# STM32_Smart.net
KiCad netlist of a schematic drawn in Altium Designer
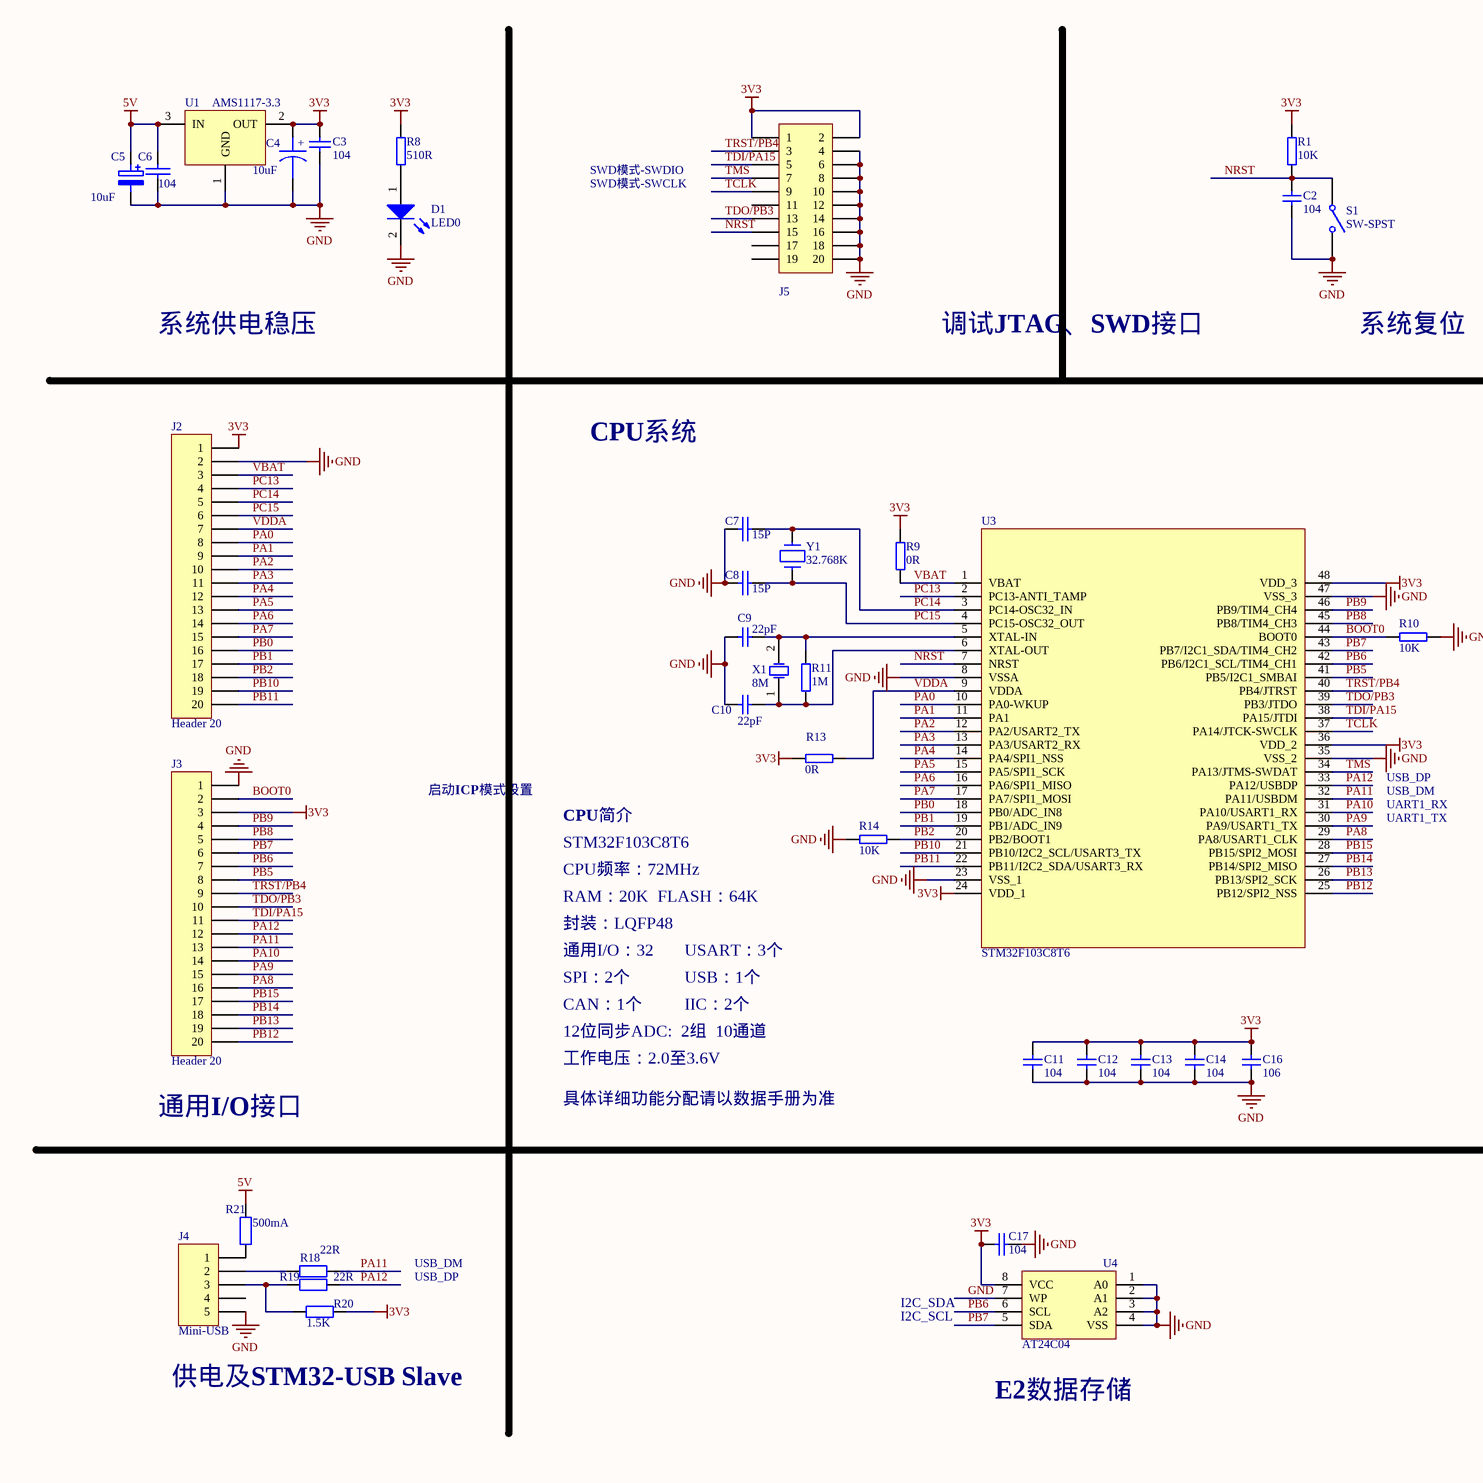
[diagram p0: STM32_Smart.SchDoc, left]
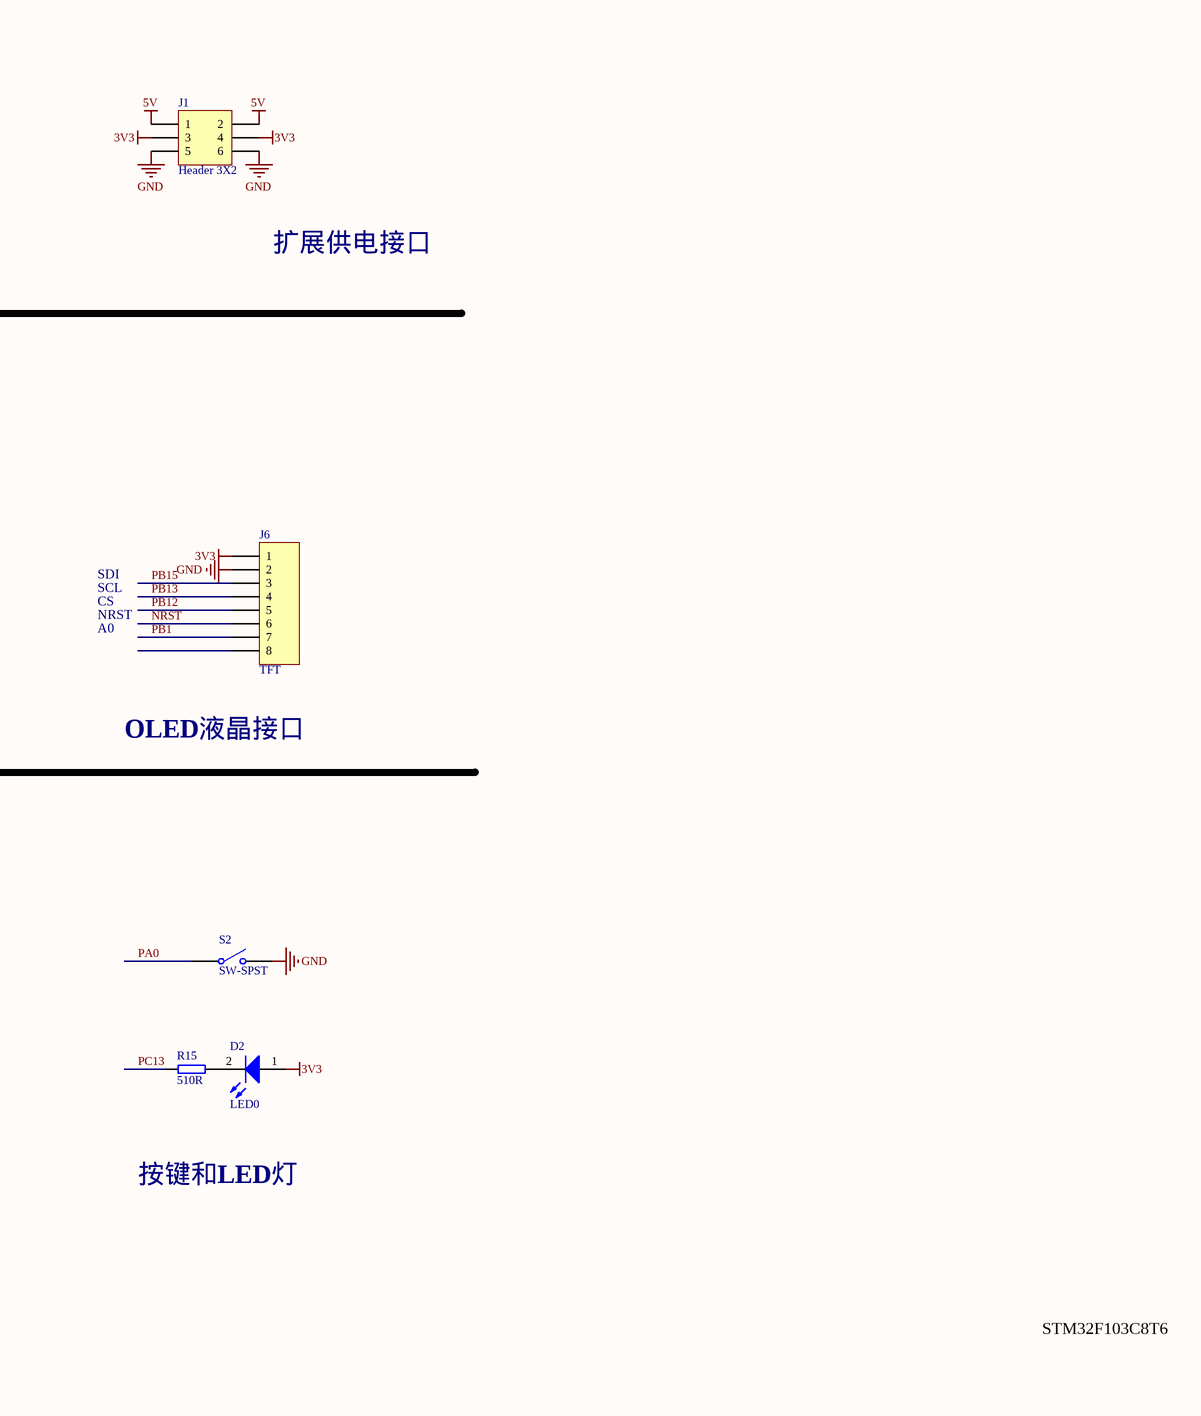
[diagram p1: STM32_Smart.SchDoc, right]

(export (version "E")
  (design (tool "Eeschema 10.0.6"))
  (components
    (comp (ref "C2")
      (value "104")
      (footprint "RC0603")
      (description "Capacitor")
      (fields (field (name "PUBLISHER") "ZL_A0OFFICE"))
      (libsource (lib "CommomDevices") (part "CAP1"))
    )
    (comp (ref "C3")
      (value "104")
      (footprint "RC0603")
      (description "Capacitor")
      (fields (field (name "PUBLISHER") "Altium Limited"))
      (libsource (lib "*") (part "Cap"))
    )
    (comp (ref "C4")
      (value "10uF")
      (footprint "RC0805")
      (description "Capacitor")
      (libsource (lib "*") (part "CAPACITOR POL"))
    )
    (comp (ref "C5") (value "10uF") (footprint "RC0805") (libsource (lib "*") (part "ELECTRO2")))
    (comp (ref "C6")
      (value "104")
      (footprint "RC0603")
      (description "Capacitor")
      (libsource (lib "") (part "CAP_1"))
    )
    (comp (ref "C7") (value "15P") (footprint "RC0603") (libsource (lib "*") (part "CAP")))
    (comp (ref "C8") (value "15P") (footprint "RC0603") (libsource (lib "*") (part "CAP")))
    (comp (ref "C9")
      (value "22pF")
      (footprint "RC0603")
      (description "Capacitor")
      (fields (field (name "PUBLISHER") "ZL_A0OFFICE"))
      (libsource (lib "CommomDevices") (part "CAP1"))
    )
    (comp (ref "C10")
      (value "22pF")
      (footprint "RC0603")
      (description "Capacitor")
      (fields (field (name "PUBLISHER") "ZL_A0OFFICE"))
      (libsource (lib "CommomDevices") (part "CAP1"))
    )
    (comp (ref "C11")
      (value "104")
      (footprint "RC0603")
      (description "Capacitor")
      (fields (field (name "PUBLISHER") "ZL_A0OFFICE"))
      (libsource (lib "CommomDevices") (part "CAP1"))
    )
    (comp (ref "C12")
      (value "104")
      (footprint "RC0603")
      (description "Capacitor")
      (fields (field (name "PUBLISHER") "ZL_A0OFFICE"))
      (libsource (lib "CommomDevices") (part "CAP1"))
    )
    (comp (ref "C13")
      (value "104")
      (footprint "RC0603")
      (description "Capacitor")
      (fields (field (name "PUBLISHER") "ZL_A0OFFICE"))
      (libsource (lib "CommomDevices") (part "CAP1"))
    )
    (comp (ref "C14")
      (value "104")
      (footprint "RC0603")
      (description "Capacitor")
      (fields (field (name "PUBLISHER") "ZL_A0OFFICE"))
      (libsource (lib "CommomDevices") (part "CAP1"))
    )
    (comp (ref "C16")
      (value "106")
      (footprint "RC0805")
      (description "Capacitor")
      (fields (field (name "PUBLISHER") "ZL_A0OFFICE"))
      (libsource (lib "CommomDevices") (part "CAP1"))
    )
    (comp (ref "C17")
      (value "104")
      (footprint "RC0603")
      (description "Capacitor")
      (libsource (lib "Miscellaneous Devices") (part "Cap"))
    )
    (comp (ref "D1")
      (value "LED0")
      (footprint "LED0805")
      (description "Typical INFRARED GaAs LED")
      (libsource (lib "Miscellaneous Devices") (part "LED0"))
    )
    (comp (ref "D2")
      (value "LED0")
      (footprint "LED0805")
      (description "Typical INFRARED GaAs LED")
      (libsource (lib "Miscellaneous Devices") (part "LED0"))
    )
    (comp (ref "J1")
      (value "Header 3X2")
      (footprint "IDE3X2-2.54")
      (description "Header, 3-Pin, Dual row")
      (fields (field (name "PUBLISHER") "Altium Limited"))
      (libsource (lib "Miscellaneous Connectors") (part "Header 3X2"))
    )
    (comp (ref "J2")
      (value "Header 20")
      (footprint "HDR1X20")
      (description "Header, 20-Pin")
      (fields (field (name "PUBLISHER") "Altium Limited"))
      (libsource (lib "Miscellaneous Connectors") (part "Header 20"))
    )
    (comp (ref "J3")
      (value "Header 20")
      (footprint "HDR1X20")
      (description "Header, 20-Pin")
      (fields (field (name "PUBLISHER") "Altium Limited"))
      (libsource (lib "Miscellaneous Connectors") (part "Header 20"))
    )
    (comp (ref "J4")
      (value "Mini-USB")
      (footprint "mini_USB")
      (description "Header, 5-Pin")
      (libsource (lib "Miscellaneous Connectors") (part "Header 5"))
    )
    (comp (ref "J5")
      (value "~")
      (footprint "JTAG20P")
      (description "Header, 10-Pin, Dual row, Right Angle")
      (fields (field (name "PUBLISHER") "Altium Limited"))
      (libsource (lib "Miscellaneous Connectors") (part "Header 10X2H"))
    )
    (comp (ref "J6")
      (value "TFT")
      (footprint "HDR1X8")
      (description "Header, 8-Pin")
      (libsource (lib "Miscellaneous Connectors") (part "Header 8"))
    )
    (comp (ref "R1") (value "10K") (footprint "RC0603") (libsource (lib "ZIBO V2.0_Main") (part "R")))
    (comp (ref "R8") (value "510R") (footprint "RC0603") (libsource (lib "ZIBO V2.0_Main") (part "R")))
    (comp (ref "R9") (value "0R") (footprint "RC0603") (libsource (lib "ZIBO V2.0_Main") (part "R")))
    (comp (ref "R10") (value "10K") (footprint "RC0603") (libsource (lib "ZIBO V2.0_Main") (part "R")))
    (comp (ref "R11") (value "1M") (footprint "RC0603") (libsource (lib "ZIBO V2.0_Main") (part "R")))
    (comp (ref "R13") (value "0R") (footprint "RC0603") (libsource (lib "ZIBO V2.0_Main") (part "R")))
    (comp (ref "R14") (value "10K") (footprint "RC0603") (libsource (lib "ZIBO V2.0_Main") (part "R")))
    (comp (ref "R15") (value "510R") (footprint "RC0603") (libsource (lib "ZIBO V2.0_Main") (part "R")))
    (comp (ref "R18")
      (value "22R")
      (footprint "RC0603")
      (description "Resistor")
      (libsource (lib "Miscellaneous Devices") (part "Res2"))
    )
    (comp (ref "R19")
      (value "22R")
      (footprint "RC0603")
      (description "Resistor")
      (libsource (lib "Miscellaneous Devices") (part "Res2"))
    )
    (comp (ref "R20")
      (value "1.5K")
      (footprint "RC0603")
      (description "Resistor")
      (libsource (lib "Miscellaneous Devices") (part "Res2"))
    )
    (comp (ref "R21")
      (value "500mA")
      (footprint "RC0805")
      (description "Resistor")
      (libsource (lib "") (part "Res2_1"))
    )
    (comp (ref "S1")
      (value "SW-SPST")
      (footprint "SMT-KEY")
      (description "Single-Pole, Single-Throw Switch")
      (libsource (lib "Miscellaneous Devices") (part "SW-SPST"))
    )
    (comp (ref "S2")
      (value "SW-SPST")
      (footprint "SMT-KEY")
      (description "Single-Pole, Single-Throw Switch")
      (libsource (lib "Miscellaneous Devices") (part "SW-SPST"))
    )
    (comp (ref "U1")
      (value "AMS1117-3.3")
      (footprint "SOT223")
      (libsource (lib "Newcapec9263_Board_NEW") (part "LT1085CM-3.3"))
    )
    (comp (ref "U3")
      (value "STM32F103C8T6")
      (footprint "LQFP48")
      (libsource (lib "STM32_Smart") (part "STM32F103C8T6"))
    )
    (comp (ref "U4") (value "AT24C04") (footprint "SOIC-8P") (libsource (lib "Newcapec9263") (part "EPROM")))
    (comp (ref "X1")
      (value "8M")
      (footprint "SMD49S")
      (description "Crystal Oscillator")
      (fields (field (name "PUBLISHER") "ZL_A0OFFICE"))
      (libsource (lib "CommomDevices") (part "XTAL_SMD"))
    )
    (comp (ref "Y1")
      (value "32.768K")
      (footprint "JZ32768")
      (description "晶振")
      (libsource (lib "*") (part "CRYSTAL"))
    )
  )
  (nets
    (net (code "1") (name "/BOOT0") (class "Default")
      (node (ref "J3") (pin "2") (pinfunction "2_2") (pintype "passive"))
      (node (ref "R10") (pin "2") (pinfunction "2_2") (pintype "passive"))
      (node (ref "U3") (pin "44") (pinfunction "BOOT0_44") (pintype "passive"))
    )
    (net (code "2") (name "/NRST") (class "Default")
      (node (ref "C2") (pin "1") (pinfunction "1_1") (pintype "passive"))
      (node (ref "J5") (pin "15") (pinfunction "15_15") (pintype "passive"))
      (node (ref "J6") (pin "6") (pinfunction "6_6") (pintype "passive"))
      (node (ref "R1") (pin "1") (pinfunction "1_1") (pintype "passive"))
      (node (ref "S1") (pin "1") (pinfunction "COMMON_1") (pintype "passive"))
      (node (ref "U3") (pin "7") (pinfunction "NRST_7") (pintype "passive"))
    )
    (net (code "3") (name "/PA0") (class "Default")
      (node (ref "J2") (pin "8") (pinfunction "8_8") (pintype "passive"))
      (node (ref "S2") (pin "1") (pinfunction "COMMON_1") (pintype "passive"))
      (node (ref "U3") (pin "10") (pinfunction "PA0-WKUP_10") (pintype "passive"))
    )
    (net (code "4") (name "/PA1") (class "Default")
      (node (ref "J2") (pin "9") (pinfunction "9_9") (pintype "passive"))
      (node (ref "U3") (pin "11") (pinfunction "PA1_11") (pintype "passive"))
    )
    (net (code "5") (name "/PA2") (class "Default")
      (node (ref "J2") (pin "10") (pinfunction "10_10") (pintype "passive"))
      (node (ref "U3") (pin "12") (pinfunction "PA2/USART2_TX_12") (pintype "passive"))
    )
    (net (code "6") (name "/PA3") (class "Default")
      (node (ref "J2") (pin "11") (pinfunction "11_11") (pintype "passive"))
      (node (ref "U3") (pin "13") (pinfunction "PA3/USART2_RX_13") (pintype "passive"))
    )
    (net (code "7") (name "/PA4") (class "Default")
      (node (ref "J2") (pin "12") (pinfunction "12_12") (pintype "passive"))
      (node (ref "U3") (pin "14") (pinfunction "PA4/SPI1_NSS_14") (pintype "passive"))
    )
    (net (code "8") (name "/PA5") (class "Default")
      (node (ref "J2") (pin "13") (pinfunction "13_13") (pintype "passive"))
      (node (ref "U3") (pin "15") (pinfunction "PA5/SPI1_SCK_15") (pintype "passive"))
    )
    (net (code "9") (name "/PA6") (class "Default")
      (node (ref "J2") (pin "14") (pinfunction "14_14") (pintype "passive"))
      (node (ref "U3") (pin "16") (pinfunction "PA6/SPI1_MISO_16") (pintype "passive"))
    )
    (net (code "10") (name "/PA7") (class "Default")
      (node (ref "J2") (pin "15") (pinfunction "15_15") (pintype "passive"))
      (node (ref "U3") (pin "17") (pinfunction "PA7/SPI1_MOSI_17") (pintype "passive"))
    )
    (net (code "11") (name "/PA8") (class "Default")
      (node (ref "J3") (pin "16") (pinfunction "16_16") (pintype "passive"))
      (node (ref "U3") (pin "29") (pinfunction "PA8/USART1_CLK_29") (pintype "passive"))
    )
    (net (code "12") (name "/PA9") (class "Default")
      (node (ref "J3") (pin "15") (pinfunction "15_15") (pintype "passive"))
      (node (ref "U3") (pin "30") (pinfunction "PA9/USART1_TX_30") (pintype "passive"))
    )
    (net (code "13") (name "/PA10") (class "Default")
      (node (ref "J3") (pin "14") (pinfunction "14_14") (pintype "passive"))
      (node (ref "U3") (pin "31") (pinfunction "PA10/USART1_RX_31") (pintype "passive"))
    )
    (net (code "14") (name "/PA11") (class "Default")
      (node (ref "J3") (pin "13") (pinfunction "13_13") (pintype "passive"))
      (node (ref "R18") (pin "1") (pinfunction "1_1") (pintype "passive"))
      (node (ref "U3") (pin "32") (pinfunction "PA11/USBDM_32") (pintype "passive"))
    )
    (net (code "15") (name "/PA12") (class "Default")
      (node (ref "J3") (pin "12") (pinfunction "12_12") (pintype "passive"))
      (node (ref "R19") (pin "1") (pinfunction "1_1") (pintype "passive"))
      (node (ref "U3") (pin "33") (pinfunction "PA12/USBDP_33") (pintype "passive"))
    )
    (net (code "16") (name "/PB0") (class "Default")
      (node (ref "J2") (pin "16") (pinfunction "16_16") (pintype "passive"))
      (node (ref "U3") (pin "18") (pinfunction "PB0/ADC_IN8_18") (pintype "passive"))
    )
    (net (code "17") (name "/PB1") (class "Default")
      (node (ref "J2") (pin "17") (pinfunction "17_17") (pintype "passive"))
      (node (ref "J6") (pin "7") (pinfunction "7_7") (pintype "passive"))
      (node (ref "U3") (pin "19") (pinfunction "PB1/ADC_IN9_19") (pintype "passive"))
    )
    (net (code "18") (name "/PB2") (class "Default")
      (node (ref "J2") (pin "18") (pinfunction "18_18") (pintype "passive"))
      (node (ref "R14") (pin "1") (pinfunction "1_1") (pintype "passive"))
      (node (ref "U3") (pin "20") (pinfunction "PB2/BOOT1_20") (pintype "passive"))
    )
    (net (code "19") (name "/PB5") (class "Default")
      (node (ref "J3") (pin "8") (pinfunction "8_8") (pintype "passive"))
      (node (ref "U3") (pin "41") (pinfunction "PB5/I2C1_SMBAI_41") (pintype "passive"))
    )
    (net (code "20") (name "/PB6") (class "Default")
      (node (ref "J3") (pin "7") (pinfunction "7_7") (pintype "passive"))
      (node (ref "U3") (pin "42") (pinfunction "PB6/I2C1_SCL/TIM4_CH1_42") (pintype "passive"))
      (node (ref "U4") (pin "6") (pinfunction "SCL_6") (pintype "passive"))
    )
    (net (code "21") (name "/PB7") (class "Default")
      (node (ref "J3") (pin "6") (pinfunction "6_6") (pintype "passive"))
      (node (ref "U3") (pin "43") (pinfunction "PB7/I2C1_SDA/TIM4_CH2_43") (pintype "passive"))
      (node (ref "U4") (pin "5") (pinfunction "SDA_5") (pintype "passive"))
    )
    (net (code "22") (name "/PB8") (class "Default")
      (node (ref "J3") (pin "5") (pinfunction "5_5") (pintype "passive"))
      (node (ref "U3") (pin "45") (pinfunction "PB8/TIM4_CH3_45") (pintype "passive"))
    )
    (net (code "23") (name "/PB9") (class "Default")
      (node (ref "J3") (pin "4") (pinfunction "4_4") (pintype "passive"))
      (node (ref "U3") (pin "46") (pinfunction "PB9/TIM4_CH4_46") (pintype "passive"))
    )
    (net (code "24") (name "/PB10") (class "Default")
      (node (ref "J2") (pin "19") (pinfunction "19_19") (pintype "passive"))
      (node (ref "U3") (pin "21") (pinfunction "PB10/I2C2_SCL/USART3_TX_21") (pintype "passive"))
    )
    (net (code "25") (name "/PB11") (class "Default")
      (node (ref "J2") (pin "20") (pinfunction "20_20") (pintype "passive"))
      (node (ref "U3") (pin "22") (pinfunction "PB11/I2C2_SDA/USART3_RX_22") (pintype "passive"))
    )
    (net (code "26") (name "/PB12") (class "Default")
      (node (ref "J3") (pin "20") (pinfunction "20_20") (pintype "passive"))
      (node (ref "J6") (pin "5") (pinfunction "5_5") (pintype "passive"))
      (node (ref "U3") (pin "25") (pinfunction "PB12/SPI2_NSS_25") (pintype "passive"))
    )
    (net (code "27") (name "/PB13") (class "Default")
      (node (ref "J3") (pin "19") (pinfunction "19_19") (pintype "passive"))
      (node (ref "J6") (pin "4") (pinfunction "4_4") (pintype "passive"))
      (node (ref "U3") (pin "26") (pinfunction "PB13/SPI2_SCK_26") (pintype "passive"))
    )
    (net (code "28") (name "/PB14") (class "Default")
      (node (ref "J3") (pin "18") (pinfunction "18_18") (pintype "passive"))
      (node (ref "U3") (pin "27") (pinfunction "PB14/SPI2_MISO_27") (pintype "passive"))
    )
    (net (code "29") (name "/PB15") (class "Default")
      (node (ref "J3") (pin "17") (pinfunction "17_17") (pintype "passive"))
      (node (ref "J6") (pin "3") (pinfunction "3_3") (pintype "passive"))
      (node (ref "U3") (pin "28") (pinfunction "PB15/SPI2_MOSI_28") (pintype "passive"))
    )
    (net (code "30") (name "/PC13") (class "Default")
      (node (ref "J2") (pin "4") (pinfunction "4_4") (pintype "passive"))
      (node (ref "R15") (pin "1") (pinfunction "1_1") (pintype "passive"))
      (node (ref "U3") (pin "2") (pinfunction "PC13-ANTI_TAMP_2") (pintype "passive"))
    )
    (net (code "31") (name "/PC14") (class "Default")
      (node (ref "C7") (pin "2") (pintype "passive"))
      (node (ref "J2") (pin "5") (pinfunction "5_5") (pintype "passive"))
      (node (ref "U3") (pin "3") (pinfunction "PC14-OSC32_IN_3") (pintype "passive"))
      (node (ref "Y1") (pin "2") (pintype "passive"))
    )
    (net (code "32") (name "/PC15") (class "Default")
      (node (ref "C8") (pin "2") (pintype "passive"))
      (node (ref "J2") (pin "6") (pinfunction "6_6") (pintype "passive"))
      (node (ref "U3") (pin "4") (pinfunction "PC15-OSC32_OUT_4") (pintype "passive"))
      (node (ref "Y1") (pin "1") (pintype "passive"))
    )
    (net (code "33") (name "/TCLK") (class "Default")
      (node (ref "J5") (pin "9") (pinfunction "9_9") (pintype "passive"))
      (node (ref "U3") (pin "37") (pinfunction "PA14/JTCK-SWCLK_37") (pintype "passive"))
    )
    (net (code "34") (name "/TDI{slash}PA15") (class "Default")
      (node (ref "J3") (pin "11") (pinfunction "11_11") (pintype "passive"))
      (node (ref "J5") (pin "5") (pinfunction "5_5") (pintype "passive"))
      (node (ref "U3") (pin "38") (pinfunction "PA15/JTDI_38") (pintype "passive"))
    )
    (net (code "35") (name "/TDO{slash}PB3") (class "Default")
      (node (ref "J3") (pin "10") (pinfunction "10_10") (pintype "passive"))
      (node (ref "J5") (pin "13") (pinfunction "13_13") (pintype "passive"))
      (node (ref "U3") (pin "39") (pinfunction "PB3/JTDO_39") (pintype "passive"))
    )
    (net (code "36") (name "/TMS") (class "Default")
      (node (ref "J5") (pin "7") (pinfunction "7_7") (pintype "passive"))
      (node (ref "U3") (pin "34") (pinfunction "PA13/JTMS-SWDAT_34") (pintype "passive"))
    )
    (net (code "37") (name "/TRST{slash}PB4") (class "Default")
      (node (ref "J3") (pin "9") (pinfunction "9_9") (pintype "passive"))
      (node (ref "J5") (pin "3") (pinfunction "3_3") (pintype "passive"))
      (node (ref "U3") (pin "40") (pinfunction "PB4/JTRST_40") (pintype "passive"))
    )
    (net (code "38") (name "/VBAT") (class "Default")
      (node (ref "J2") (pin "3") (pinfunction "3_3") (pintype "passive"))
      (node (ref "R9") (pin "1") (pinfunction "1_1") (pintype "passive"))
      (node (ref "U3") (pin "1") (pinfunction "VBAT_1") (pintype "passive"))
    )
    (net (code "39") (name "/VDDA") (class "Default")
      (node (ref "J2") (pin "7") (pinfunction "7_7") (pintype "passive"))
      (node (ref "R13") (pin "1") (pinfunction "1_1") (pintype "passive"))
      (node (ref "U3") (pin "9") (pinfunction "VDDA_9") (pintype "passive"))
    )
    (net (code "40") (name "3V3") (class "Default")
      (node (ref "C11") (pin "1") (pinfunction "1_1") (pintype "passive"))
      (node (ref "C12") (pin "1") (pinfunction "1_1") (pintype "passive"))
      (node (ref "C13") (pin "1") (pinfunction "1_1") (pintype "passive"))
      (node (ref "C14") (pin "1") (pinfunction "1_1") (pintype "passive"))
      (node (ref "C16") (pin "1") (pinfunction "1_1") (pintype "passive"))
      (node (ref "C17") (pin "2") (pinfunction "2_2") (pintype "passive"))
      (node (ref "C3") (pin "1") (pinfunction "1_1") (pintype "passive"))
      (node (ref "C4") (pin "1") (pinfunction "1_1") (pintype "passive"))
      (node (ref "D2") (pin "1") (pinfunction "A_1") (pintype "passive"))
      (node (ref "J1") (pin "3") (pinfunction "3_3") (pintype "passive"))
      (node (ref "J1") (pin "4") (pinfunction "4_4") (pintype "passive"))
      (node (ref "J2") (pin "1") (pinfunction "1_1") (pintype "passive"))
      (node (ref "J3") (pin "3") (pinfunction "3_3") (pintype "passive"))
      (node (ref "J5") (pin "1") (pinfunction "1_1") (pintype "passive"))
      (node (ref "J5") (pin "2") (pinfunction "2_2") (pintype "passive"))
      (node (ref "J6") (pin "1") (pinfunction "1_1") (pintype "passive"))
      (node (ref "R1") (pin "2") (pinfunction "2_2") (pintype "passive"))
      (node (ref "R13") (pin "2") (pinfunction "2_2") (pintype "passive"))
      (node (ref "R20") (pin "1") (pinfunction "1_1") (pintype "passive"))
      (node (ref "R8") (pin "2") (pinfunction "2_2") (pintype "passive"))
      (node (ref "R9") (pin "2") (pinfunction "2_2") (pintype "passive"))
      (node (ref "U1") (pin "2") (pinfunction "OUT_2") (pintype "passive"))
      (node (ref "U3") (pin "24") (pinfunction "VDD_1_24") (pintype "passive"))
      (node (ref "U3") (pin "36") (pinfunction "VDD_2_36") (pintype "passive"))
      (node (ref "U3") (pin "48") (pinfunction "VDD_3_48") (pintype "passive"))
      (node (ref "U4") (pin "8") (pinfunction "VCC_8") (pintype "passive"))
    )
    (net (code "41") (name "5V") (class "Default")
      (node (ref "C5") (pin "1") (pintype "passive"))
      (node (ref "C6") (pin "1") (pinfunction "1_1") (pintype "passive"))
      (node (ref "J1") (pin "1") (pinfunction "1_1") (pintype "passive"))
      (node (ref "J1") (pin "2") (pinfunction "2_2") (pintype "passive"))
      (node (ref "R21") (pin "1") (pinfunction "1_1") (pintype "passive"))
      (node (ref "U1") (pin "3") (pinfunction "IN_3") (pintype "passive"))
    )
    (net (code "42") (name "GND") (class "Default")
      (node (ref "C10") (pin "2") (pinfunction "2_2") (pintype "passive"))
      (node (ref "C11") (pin "2") (pinfunction "2_2") (pintype "passive"))
      (node (ref "C12") (pin "2") (pinfunction "2_2") (pintype "passive"))
      (node (ref "C13") (pin "2") (pinfunction "2_2") (pintype "passive"))
      (node (ref "C14") (pin "2") (pinfunction "2_2") (pintype "passive"))
      (node (ref "C16") (pin "2") (pinfunction "2_2") (pintype "passive"))
      (node (ref "C17") (pin "1") (pinfunction "1_1") (pintype "passive"))
      (node (ref "C2") (pin "2") (pinfunction "2_2") (pintype "passive"))
      (node (ref "C3") (pin "2") (pinfunction "2_2") (pintype "passive"))
      (node (ref "C4") (pin "2") (pinfunction "2_2") (pintype "passive"))
      (node (ref "C5") (pin "2") (pintype "passive"))
      (node (ref "C6") (pin "2") (pinfunction "2_2") (pintype "passive"))
      (node (ref "C7") (pin "1") (pintype "passive"))
      (node (ref "C8") (pin "1") (pintype "passive"))
      (node (ref "C9") (pin "2") (pinfunction "2_2") (pintype "passive"))
      (node (ref "D1") (pin "2") (pinfunction "K_2") (pintype "passive"))
      (node (ref "J1") (pin "5") (pinfunction "5_5") (pintype "passive"))
      (node (ref "J1") (pin "6") (pinfunction "6_6") (pintype "passive"))
      (node (ref "J2") (pin "2") (pinfunction "2_2") (pintype "passive"))
      (node (ref "J3") (pin "1") (pinfunction "1_1") (pintype "passive"))
      (node (ref "J4") (pin "5") (pinfunction "5_5") (pintype "passive"))
      (node (ref "J5") (pin "10") (pinfunction "10_10") (pintype "passive"))
      (node (ref "J5") (pin "12") (pinfunction "12_12") (pintype "passive"))
      (node (ref "J5") (pin "14") (pinfunction "14_14") (pintype "passive"))
      (node (ref "J5") (pin "16") (pinfunction "16_16") (pintype "passive"))
      (node (ref "J5") (pin "18") (pinfunction "18_18") (pintype "passive"))
      (node (ref "J5") (pin "20") (pinfunction "20_20") (pintype "passive"))
      (node (ref "J5") (pin "4") (pinfunction "4_4") (pintype "passive"))
      (node (ref "J5") (pin "6") (pinfunction "6_6") (pintype "passive"))
      (node (ref "J5") (pin "8") (pinfunction "8_8") (pintype "passive"))
      (node (ref "J6") (pin "2") (pinfunction "2_2") (pintype "passive"))
      (node (ref "R10") (pin "1") (pinfunction "1_1") (pintype "passive"))
      (node (ref "R14") (pin "2") (pinfunction "2_2") (pintype "passive"))
      (node (ref "S1") (pin "2") (pinfunction "NO_2") (pintype "passive"))
      (node (ref "S2") (pin "2") (pinfunction "NO_2") (pintype "passive"))
      (node (ref "U1") (pin "1") (pinfunction "GND_1") (pintype "passive"))
      (node (ref "U3") (pin "23") (pinfunction "VSS_1_23") (pintype "passive"))
      (node (ref "U3") (pin "35") (pinfunction "VSS_2_35") (pintype "passive"))
      (node (ref "U3") (pin "47") (pinfunction "VSS_3_47") (pintype "passive"))
      (node (ref "U3") (pin "8") (pinfunction "VSSA_8") (pintype "passive"))
      (node (ref "U4") (pin "1") (pinfunction "A0_1") (pintype "passive"))
      (node (ref "U4") (pin "2") (pinfunction "A1_2") (pintype "passive"))
      (node (ref "U4") (pin "3") (pinfunction "A2_3") (pintype "passive"))
      (node (ref "U4") (pin "4") (pinfunction "VSS_4") (pintype "passive"))
      (node (ref "U4") (pin "7") (pinfunction "WP_7") (pintype "passive"))
    )
    (net (code "43") (name "Net-(D1-A)") (class "Default")
      (node (ref "D1") (pin "1") (pinfunction "A_1") (pintype "passive"))
      (node (ref "R8") (pin "1") (pinfunction "1_1") (pintype "passive"))
    )
    (net (code "44") (name "Net-(D2-K)") (class "Default")
      (node (ref "D2") (pin "2") (pinfunction "K_2") (pintype "passive"))
      (node (ref "R15") (pin "2") (pinfunction "2_2") (pintype "passive"))
    )
    (net (code "45") (name "Net-(J4-Pad1)") (class "Default")
      (node (ref "J4") (pin "1") (pinfunction "1_1") (pintype "passive"))
      (node (ref "R21") (pin "2") (pinfunction "2_2") (pintype "passive"))
    )
    (net (code "46") (name "Net-(J4-Pad2)") (class "Default")
      (node (ref "J4") (pin "2") (pinfunction "2_2") (pintype "passive"))
      (node (ref "R18") (pin "2") (pinfunction "2_2") (pintype "passive"))
    )
    (net (code "47") (name "Net-(J4-Pad3)") (class "Default")
      (node (ref "J4") (pin "3") (pinfunction "3_3") (pintype "passive"))
      (node (ref "R19") (pin "2") (pinfunction "2_2") (pintype "passive"))
      (node (ref "R20") (pin "2") (pinfunction "2_2") (pintype "passive"))
    )
    (net (code "48") (name "Net-(U3-XTAL-IN)") (class "Default")
      (node (ref "C9") (pin "1") (pinfunction "1_1") (pintype "passive"))
      (node (ref "R11") (pin "2") (pinfunction "2_2") (pintype "passive"))
      (node (ref "U3") (pin "5") (pinfunction "XTAL-IN_5") (pintype "passive"))
      (node (ref "X1") (pin "2") (pinfunction "2_2") (pintype "passive"))
    )
    (net (code "49") (name "Net-(U3-XTAL-OUT)") (class "Default")
      (node (ref "C10") (pin "1") (pinfunction "1_1") (pintype "passive"))
      (node (ref "R11") (pin "1") (pinfunction "1_1") (pintype "passive"))
      (node (ref "U3") (pin "6") (pinfunction "XTAL-OUT_6") (pintype "passive"))
      (node (ref "X1") (pin "1") (pinfunction "1_1") (pintype "passive"))
    )
    (net (code "50") (name "unconnected-(J4-Pad4)") (class "Default")
      (node (ref "J4") (pin "4") (pinfunction "4_4") (pintype "passive"))
    )
    (net (code "51") (name "unconnected-(J5-Pad11)") (class "Default")
      (node (ref "J5") (pin "11") (pinfunction "11_11") (pintype "passive"))
    )
    (net (code "52") (name "unconnected-(J5-Pad17)") (class "Default")
      (node (ref "J5") (pin "17") (pinfunction "17_17") (pintype "passive"))
    )
    (net (code "53") (name "unconnected-(J5-Pad19)") (class "Default")
      (node (ref "J5") (pin "19") (pinfunction "19_19") (pintype "passive"))
    )
    (net (code "54") (name "unconnected-(J6-Pad8)") (class "Default")
      (node (ref "J6") (pin "8") (pinfunction "8_8") (pintype "passive"))
    )
  )
)
